# ESP8266.net
KiCad netlist of a schematic drawn in Altium Designer
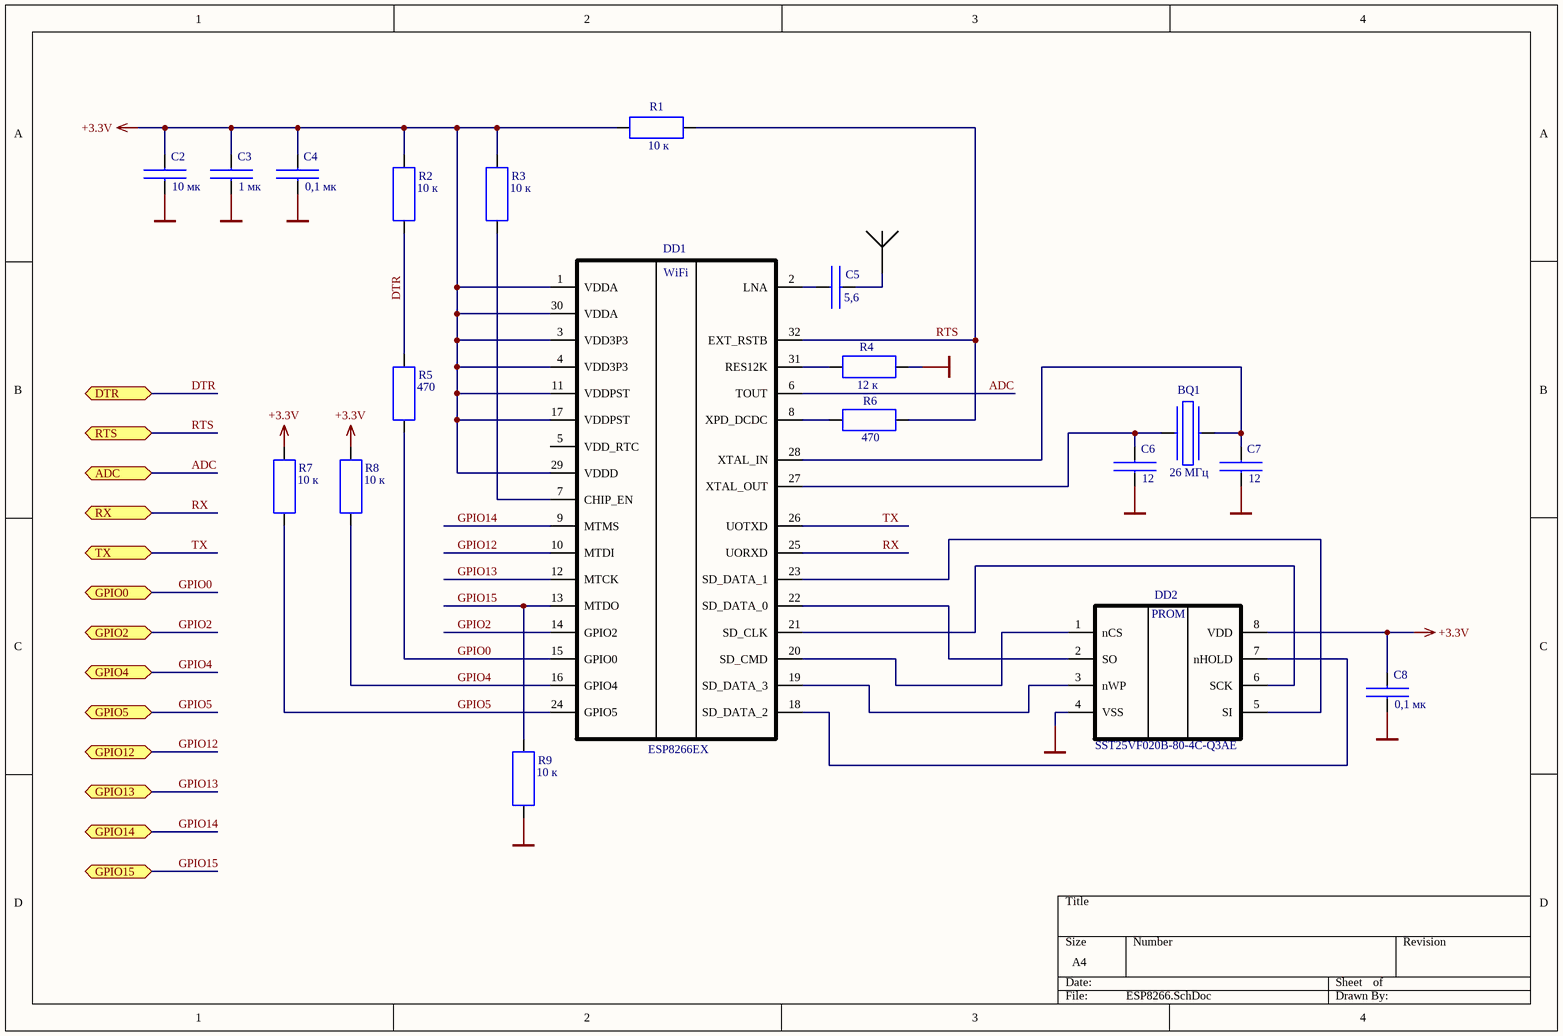
[diagram p0: ESP8266.SchDoc]

(export (version "E")
  (design (tool "Eeschema 10.0.6"))
  (components
    (comp (ref "A1")
      (value "2.4 GHz")
      (footprint "Ant_2.4G")
      (description "2.4 GHz PCB  Meandered  Inverted-F Antenna")
      (libsource (lib "clock2") (part "Mean_Inverted_F_2.4G"))
    )
    (comp (ref "BQ1") (value "26 МГц") (footprint "OSC2520") (libsource (lib "clock2") (part "OSC2520")))
    (comp (ref "C2")
      (value "10 мк")
      (footprint "CC1608(0603)x09")
      (description "Ceramic Chip-capacitor 0603")
      (fields (field (name "VOLTAGE") "25 / 16"))
      (libsource (lib "PCB_Project1_6") (part "CC0603 X7R uF0.22 V25/16"))
    )
    (comp (ref "C3")
      (value "1 мк")
      (footprint "CC1608(0603)x09")
      (description "Ceramic Chip-capacitor 0603")
      (fields (field (name "VOLTAGE") "25 / 16"))
      (libsource (lib "PCB_Project1_6") (part "CC0603 X7R uF0.22 V25/16"))
    )
    (comp (ref "C4")
      (value "0,1 мк")
      (footprint "CC1608(0603)x09")
      (description "Ceramic Chip-capacitor 0603")
      (fields (field (name "VOLTAGE") "25 / 16"))
      (libsource (lib "PCB_Project1_6") (part "CC0603 X7R uF0.22 V25/16"))
    )
    (comp (ref "C5")
      (value "5,6")
      (footprint "CC1608(0603)x09")
      (description "Ceramic Chip-capacitor 0603")
      (fields (field (name "VOLTAGE") "25 / 16"))
      (libsource (lib "PCB_Project1_6") (part "CC0603 X7R uF0.22 V25/16"))
    )
    (comp (ref "C6")
      (value "12")
      (footprint "CC1608(0603)x09")
      (description "Ceramic Chip-capacitor 0603")
      (fields (field (name "VOLTAGE") "25 / 16"))
      (libsource (lib "PCB_Project1_6") (part "CC0603 X7R uF0.22 V25/16"))
    )
    (comp (ref "C7")
      (value "12")
      (footprint "CC1608(0603)x09")
      (description "Ceramic Chip-capacitor 0603")
      (fields (field (name "VOLTAGE") "25 / 16"))
      (libsource (lib "PCB_Project1_6") (part "CC0603 X7R uF0.22 V25/16"))
    )
    (comp (ref "C8")
      (value "0,1 мк")
      (footprint "CC1608(0603)x09")
      (description "Ceramic Chip-capacitor 0603")
      (fields (field (name "VOLTAGE") "25 / 16"))
      (libsource (lib "PCB_Project1_6") (part "CC0603 X7R uF0.22 V25/16"))
    )
    (comp (ref "DD1")
      (value "ESP8266EX")
      (footprint "QFN50P500X500X90_HS-33N")
      (libsource (lib "clock2") (part "ESP8622EX"))
    )
    (comp (ref "DD2")
      (value "SST25VF020B-80-4C-Q3AE")
      (footprint "SON127P600-8N")
      (libsource (lib "clock2") (part "SST25VF020B-80-4C-Q3AE"))
    )
    (comp (ref "R1")
      (value "10 к")
      (footprint "RC1608(0603)x06")
      (description "Chip Resistor 0603")
      (libsource (lib "clock2") (part "1% R0603-K15.0"))
    )
    (comp (ref "R2")
      (value "10 к")
      (footprint "RC1608(0603)x06")
      (description "Chip Resistor 0603")
      (libsource (lib "clock2") (part "1% R0603-K15.0"))
    )
    (comp (ref "R3")
      (value "10 к")
      (footprint "RC1608(0603)x06")
      (description "Chip Resistor 0603")
      (libsource (lib "clock2") (part "1% R0603-K15.0"))
    )
    (comp (ref "R4")
      (value "12 к")
      (footprint "RC1608(0603)x06")
      (description "Chip Resistor 0603")
      (libsource (lib "clock2") (part "1% R0603-K15.0"))
    )
    (comp (ref "R5")
      (value "470")
      (footprint "RC1608(0603)x06")
      (description "Chip Resistor 0603")
      (libsource (lib "clock2") (part "1% R0603-K15.0"))
    )
    (comp (ref "R6")
      (value "470")
      (footprint "RC1608(0603)x06")
      (description "Chip Resistor 0603")
      (libsource (lib "clock2") (part "1% R0603-K15.0"))
    )
    (comp (ref "R7")
      (value "10 к")
      (footprint "RC1608(0603)x06")
      (description "Chip Resistor 0603")
      (libsource (lib "clock2") (part "1% R0603-K15.0"))
    )
    (comp (ref "R8")
      (value "10 к")
      (footprint "RC1608(0603)x06")
      (description "Chip Resistor 0603")
      (libsource (lib "clock2") (part "1% R0603-K15.0"))
    )
    (comp (ref "R9")
      (value "10 к")
      (footprint "RC1608(0603)x06")
      (description "Chip Resistor 0603")
      (libsource (lib "clock2") (part "1% R0603-K15.0"))
    )
  )
  (nets
    (net (code "1") (name "+3.3V") (class "Default")
      (node (ref "C2") (pin "1") (pintype "passive"))
      (node (ref "C3") (pin "1") (pintype "passive"))
      (node (ref "C4") (pin "1") (pintype "passive"))
      (node (ref "C8") (pin "1") (pintype "passive"))
      (node (ref "DD1") (pin "1") (pinfunction "VDDA_1") (pintype "passive"))
      (node (ref "DD1") (pin "11") (pinfunction "VDDPST_11") (pintype "passive"))
      (node (ref "DD1") (pin "17") (pinfunction "VDDPST_17") (pintype "passive"))
      (node (ref "DD1") (pin "29") (pinfunction "VDDD_29") (pintype "passive"))
      (node (ref "DD1") (pin "3") (pinfunction "VDD3P3_3") (pintype "passive"))
      (node (ref "DD1") (pin "30") (pinfunction "VDDA_30") (pintype "passive"))
      (node (ref "DD1") (pin "4") (pinfunction "VDD3P3_4") (pintype "passive"))
      (node (ref "DD2") (pin "8") (pinfunction "VDD_8") (pintype "passive"))
      (node (ref "R1") (pin "2") (pintype "passive"))
      (node (ref "R2") (pin "2") (pintype "passive"))
      (node (ref "R3") (pin "2") (pintype "passive"))
      (node (ref "R7") (pin "2") (pintype "passive"))
      (node (ref "R8") (pin "2") (pintype "passive"))
    )
    (net (code "2") (name "/ADC") (class "Default")
      (node (ref "DD1") (pin "6") (pinfunction "TOUT_6") (pintype "passive"))
    )
    (net (code "3") (name "/DTR") (class "Default")
      (node (ref "R2") (pin "1") (pintype "passive"))
      (node (ref "R5") (pin "2") (pintype "passive"))
    )
    (net (code "4") (name "/GPIO0") (class "Default")
      (node (ref "DD1") (pin "15") (pinfunction "GPIO0_15") (pintype "passive"))
      (node (ref "R5") (pin "1") (pintype "passive"))
    )
    (net (code "5") (name "/GPIO2") (class "Default")
      (node (ref "DD1") (pin "14") (pinfunction "GPIO2_14") (pintype "passive"))
    )
    (net (code "6") (name "/GPIO4") (class "Default")
      (node (ref "DD1") (pin "16") (pinfunction "GPIO4_16") (pintype "passive"))
      (node (ref "R8") (pin "1") (pintype "passive"))
    )
    (net (code "7") (name "/GPIO5") (class "Default")
      (node (ref "DD1") (pin "24") (pinfunction "GPIO5_24") (pintype "passive"))
      (node (ref "R7") (pin "1") (pintype "passive"))
    )
    (net (code "8") (name "/GPIO12") (class "Default")
      (node (ref "DD1") (pin "10") (pinfunction "MTDI_10") (pintype "passive"))
    )
    (net (code "9") (name "/GPIO13") (class "Default")
      (node (ref "DD1") (pin "12") (pinfunction "MTCK_12") (pintype "passive"))
    )
    (net (code "10") (name "/GPIO14") (class "Default")
      (node (ref "DD1") (pin "9") (pinfunction "MTMS_9") (pintype "passive"))
    )
    (net (code "11") (name "/GPIO15") (class "Default")
      (node (ref "DD1") (pin "13") (pinfunction "MTDO_13") (pintype "passive"))
      (node (ref "R9") (pin "2") (pintype "passive"))
    )
    (net (code "12") (name "/RTS") (class "Default")
      (node (ref "DD1") (pin "32") (pinfunction "EXT_RSTB_32") (pintype "passive"))
      (node (ref "R1") (pin "1") (pintype "passive"))
      (node (ref "R6") (pin "1") (pintype "passive"))
    )
    (net (code "13") (name "/RX") (class "Default")
      (node (ref "DD1") (pin "25") (pinfunction "UORXD_25") (pintype "passive"))
    )
    (net (code "14") (name "/TX") (class "Default")
      (node (ref "DD1") (pin "26") (pinfunction "UOTXD_26") (pintype "passive"))
    )
    (net (code "15") (name "GND") (class "Default")
      (node (ref "C2") (pin "2") (pintype "passive"))
      (node (ref "C3") (pin "2") (pintype "passive"))
      (node (ref "C4") (pin "2") (pintype "passive"))
      (node (ref "C6") (pin "2") (pintype "passive"))
      (node (ref "C7") (pin "2") (pintype "passive"))
      (node (ref "C8") (pin "2") (pintype "passive"))
      (node (ref "DD1") (pin "33") (pinfunction "GND_33") (pintype "power_in"))
      (node (ref "DD2") (pin "4") (pinfunction "VSS_4") (pintype "passive"))
      (node (ref "R4") (pin "1") (pintype "passive"))
      (node (ref "R9") (pin "1") (pintype "passive"))
    )
    (net (code "16") (name "Net-(A1-Pad1)") (class "Default")
      (node (ref "A1") (pin "1") (pintype "passive"))
      (node (ref "C5") (pin "2") (pintype "passive"))
    )
    (net (code "17") (name "Net-(DD1-CHIP_EN)") (class "Default")
      (node (ref "DD1") (pin "7") (pinfunction "CHIP_EN_7") (pintype "passive"))
      (node (ref "R3") (pin "1") (pintype "passive"))
    )
    (net (code "18") (name "Net-(DD1-LNA)") (class "Default")
      (node (ref "C5") (pin "1") (pintype "passive"))
      (node (ref "DD1") (pin "2") (pinfunction "LNA_2") (pintype "passive"))
    )
    (net (code "19") (name "Net-(DD1-RES12K)") (class "Default")
      (node (ref "DD1") (pin "31") (pinfunction "RES12K_31") (pintype "passive"))
      (node (ref "R4") (pin "2") (pintype "passive"))
    )
    (net (code "20") (name "Net-(DD1-SD_CLK)") (class "Default")
      (node (ref "DD1") (pin "21") (pinfunction "SD_CLK_21") (pintype "passive"))
      (node (ref "DD2") (pin "6") (pinfunction "SCK_6") (pintype "passive"))
    )
    (net (code "21") (name "Net-(DD1-SD_CMD)") (class "Default")
      (node (ref "DD1") (pin "20") (pinfunction "SD_CMD_20") (pintype "passive"))
      (node (ref "DD2") (pin "1") (pinfunction "nCS_1") (pintype "passive"))
    )
    (net (code "22") (name "Net-(DD1-SD_DATA_0)") (class "Default")
      (node (ref "DD1") (pin "22") (pinfunction "SD_DATA_0_22") (pintype "passive"))
      (node (ref "DD2") (pin "2") (pinfunction "SO_2") (pintype "passive"))
    )
    (net (code "23") (name "Net-(DD1-SD_DATA_1)") (class "Default")
      (node (ref "DD1") (pin "23") (pinfunction "SD_DATA_1_23") (pintype "passive"))
      (node (ref "DD2") (pin "5") (pinfunction "SI_5") (pintype "passive"))
    )
    (net (code "24") (name "Net-(DD1-SD_DATA_2)") (class "Default")
      (node (ref "DD1") (pin "18") (pinfunction "SD_DATA_2_18") (pintype "passive"))
      (node (ref "DD2") (pin "7") (pinfunction "nHOLD_7") (pintype "passive"))
    )
    (net (code "25") (name "Net-(DD1-SD_DATA_3)") (class "Default")
      (node (ref "DD1") (pin "19") (pinfunction "SD_DATA_3_19") (pintype "passive"))
      (node (ref "DD2") (pin "3") (pinfunction "nWP_3") (pintype "passive"))
    )
    (net (code "26") (name "Net-(DD1-XPD_DCDC)") (class "Default")
      (node (ref "DD1") (pin "8") (pinfunction "XPD_DCDC_8") (pintype "passive"))
      (node (ref "R6") (pin "2") (pintype "passive"))
    )
    (net (code "27") (name "Net-(DD1-XTAL_IN)") (class "Default")
      (node (ref "BQ1") (pin "3") (pintype "passive"))
      (node (ref "C7") (pin "1") (pintype "passive"))
      (node (ref "DD1") (pin "28") (pinfunction "XTAL_IN_28") (pintype "passive"))
    )
    (net (code "28") (name "Net-(DD1-XTAL_OUT)") (class "Default")
      (node (ref "BQ1") (pin "1") (pintype "passive"))
      (node (ref "C6") (pin "1") (pintype "passive"))
      (node (ref "DD1") (pin "27") (pinfunction "XTAL_OUT_27") (pintype "passive"))
    )
    (net (code "29") (name "unconnected-(DD1-VDD_RTC-Pad5)") (class "Default")
      (node (ref "DD1") (pin "5") (pinfunction "VDD_RTC_5") (pintype "passive"))
    )
  )
)
